# car.net
KiCad netlist of a schematic drawn in Altium Designer
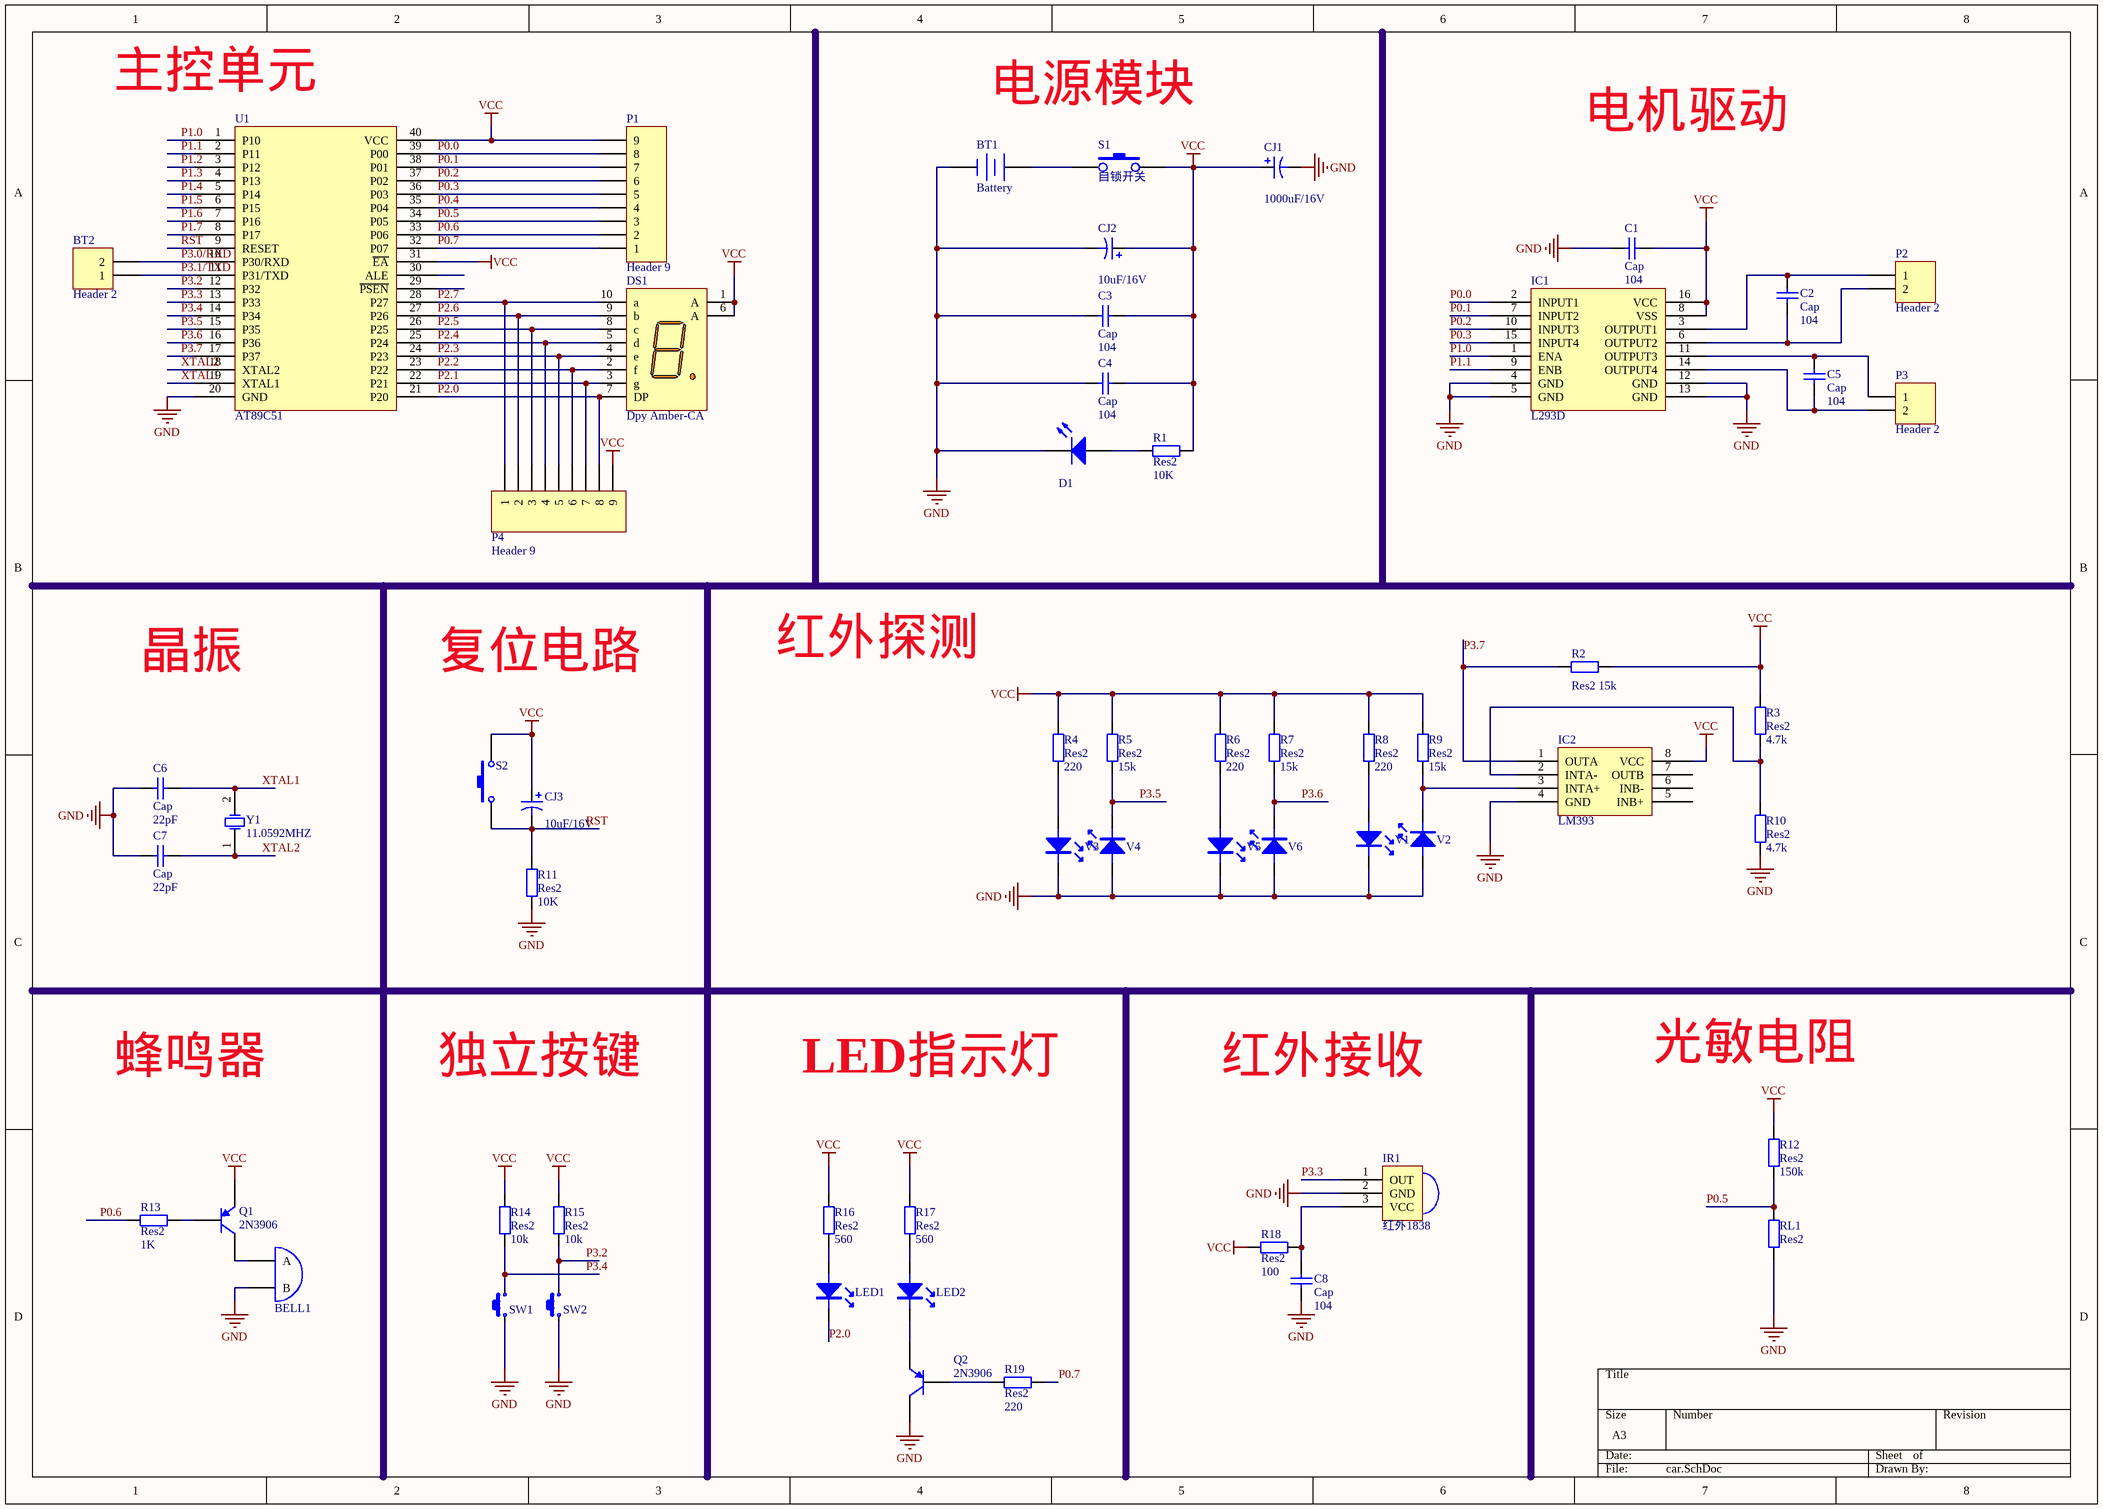
[diagram p0: car.SchDoc]

(export (version "E")
  (design (tool "Eeschema 10.0.6"))
  (components
    (comp (ref "BELL1") (value "BELL") (footprint "BELL") (libsource (lib "SQ-1") (part "BELL")))
    (comp (ref "BT1")
      (value "Battery")
      (footprint "BAT-2")
      (description "Multicell Battery")
      (fields (field (name "PUBLISHER") "Altium Limited"))
      (libsource (lib "Miscellaneous Devices") (part "Battery"))
    )
    (comp (ref "BT2")
      (value "Header 2")
      (footprint "HDR1X2")
      (description "Header, 2-Pin")
      (fields (field (name "PUBLISHER") "Altium Limited"))
      (libsource (lib "") (part "Header 2_1"))
    )
    (comp (ref "C1")
      (value "Cap")
      (footprint "0805C")
      (description "Capacitor")
      (fields (field (name "ALTIUM_VALUE") "104") (field (name "PUBLISHER") "Altium Limited"))
      (libsource (lib "Miscellaneous Devices") (part "Cap"))
    )
    (comp (ref "C2")
      (value "Cap")
      (footprint "0805C")
      (description "Capacitor")
      (fields (field (name "ALTIUM_VALUE") "104") (field (name "PUBLISHER") "Altium Limited"))
      (libsource (lib "Miscellaneous Devices") (part "Cap"))
    )
    (comp (ref "C3")
      (value "Cap")
      (footprint "0805C")
      (description "Capacitor")
      (fields (field (name "ALTIUM_VALUE") "104") (field (name "PUBLISHER") "Altium Limited"))
      (libsource (lib "Miscellaneous Devices") (part "Cap"))
    )
    (comp (ref "C4")
      (value "Cap")
      (footprint "0805C")
      (description "Capacitor")
      (fields (field (name "ALTIUM_VALUE") "104") (field (name "PUBLISHER") "Altium Limited"))
      (libsource (lib "Miscellaneous Devices") (part "Cap"))
    )
    (comp (ref "C5")
      (value "Cap")
      (footprint "0805C")
      (description "Capacitor")
      (fields (field (name "ALTIUM_VALUE") "104") (field (name "PUBLISHER") "Altium Limited"))
      (libsource (lib "Miscellaneous Devices") (part "Cap"))
    )
    (comp (ref "C6")
      (value "Cap")
      (footprint "0805C")
      (description "Capacitor")
      (fields (field (name "ALTIUM_VALUE") "22pF") (field (name "PUBLISHER") "Altium Limited"))
      (libsource (lib "Miscellaneous Devices") (part "Cap"))
    )
    (comp (ref "C7")
      (value "Cap")
      (footprint "0805C")
      (description "Capacitor")
      (fields (field (name "ALTIUM_VALUE") "22pF") (field (name "PUBLISHER") "Altium Limited"))
      (libsource (lib "Miscellaneous Devices") (part "Cap"))
    )
    (comp (ref "C8")
      (value "Cap")
      (footprint "0805C")
      (description "Capacitor")
      (fields (field (name "ALTIUM_VALUE") "104") (field (name "PUBLISHER") "Altium Limited"))
      (libsource (lib "Miscellaneous Devices") (part "Cap"))
    )
    (comp (ref "CJ1")
      (value "1000uF/16V")
      (footprint "RB10U")
      (description "Polarized Capacitor (Radial)")
      (fields (field (name "PUBLISHER") "Altium Limited"))
      (libsource (lib "Miscellaneous Devices") (part "Cap Pol1"))
    )
    (comp (ref "CJ2")
      (value "10uF/16V")
      (footprint "RB10U")
      (description "Polarized Capacitor (Radial)")
      (fields (field (name "PUBLISHER") "Altium Limited"))
      (libsource (lib "Miscellaneous Devices") (part "Cap Pol1"))
    )
    (comp (ref "CJ3")
      (value "10uF/16V")
      (footprint "RB10U")
      (description "Polarized Capacitor (Radial)")
      (fields (field (name "PUBLISHER") "Altium Limited"))
      (libsource (lib "Miscellaneous Devices") (part "Cap Pol1"))
    )
    (comp (ref "D1")
      (value "LED0")
      (footprint "0805-LED")
      (description "Typical INFRARED GaAs LED")
      (fields (field (name "PUBLISHER") "Altium Limited"))
      (libsource (lib "Miscellaneous Devices") (part "LED0"))
    )
    (comp (ref "DS1")
      (value "Dpy Amber-CA")
      (footprint "A")
      (description "7.62 mm Black Surface Orange 7-Segment Display: CA, RH DP")
      (fields (field (name "PUBLISHER") "Altium Limited"))
      (libsource (lib "Miscellaneous Devices") (part "Dpy Amber-CA"))
    )
    (comp (ref "IC1") (value "L293D") (footprint "L293D") (libsource (lib "SQ-1") (part "L293D")))
    (comp (ref "IC2") (value "LM393") (footprint "LM393") (libsource (lib "SQ-1") (part "LM393")))
    (comp (ref "IR1") (value "红外1838") (footprint "红外1838") (libsource (lib "SQ-1") (part "红外1838")))
    (comp (ref "LED1") (value "LED") (footprint "0805-LED") (libsource (lib "SQ-1") (part "LED")))
    (comp (ref "LED2") (value "LED") (footprint "0805-LED") (libsource (lib "SQ-1") (part "LED")))
    (comp (ref "P1")
      (value "Header 9")
      (footprint "HDR1X9")
      (description "Header, 9-Pin")
      (fields (field (name "PUBLISHER") "Altium Limited"))
      (libsource (lib "") (part "Header 9_1"))
    )
    (comp (ref "P2")
      (value "Header 2")
      (footprint "HDR1X2")
      (description "Header, 2-Pin")
      (fields (field (name "PUBLISHER") "Altium Limited"))
      (libsource (lib "Miscellaneous Connectors") (part "Header 2"))
    )
    (comp (ref "P3")
      (value "Header 2")
      (footprint "HDR1X2")
      (description "Header, 2-Pin")
      (fields (field (name "PUBLISHER") "Altium Limited"))
      (libsource (lib "Miscellaneous Connectors") (part "Header 2"))
    )
    (comp (ref "P4")
      (value "Header 9")
      (footprint "HDR1X9")
      (description "Header, 9-Pin")
      (fields (field (name "PUBLISHER") "Altium Limited"))
      (libsource (lib "Miscellaneous Connectors") (part "Header 9"))
    )
    (comp (ref "Q1")
      (value "2N3906")
      (footprint "TO-92A")
      (description "PNP General Purpose Amplifier")
      (fields (field (name "PUBLISHER") "Altium Limited"))
      (libsource (lib "Miscellaneous Devices") (part "2N3906"))
    )
    (comp (ref "Q2")
      (value "2N3906")
      (footprint "TO-92A")
      (description "PNP General Purpose Amplifier")
      (fields (field (name "PUBLISHER") "Altium Limited"))
      (libsource (lib "Miscellaneous Devices") (part "2N3906"))
    )
    (comp (ref "R1")
      (value "Res2")
      (footprint "0805")
      (description "Resistor")
      (fields (field (name "ALTIUM_VALUE") "10K") (field (name "PUBLISHER") "Altium Limited"))
      (libsource (lib "") (part "Res2_2"))
    )
    (comp (ref "R2")
      (value "Res2")
      (footprint "0805")
      (description "Resistor")
      (fields (field (name "ALTIUM_VALUE") "15k") (field (name "PUBLISHER") "Altium Limited"))
      (libsource (lib "") (part "Res2_3"))
    )
    (comp (ref "R3")
      (value "Res2")
      (footprint "0805")
      (description "Resistor")
      (fields (field (name "ALTIUM_VALUE") "4.7k") (field (name "PUBLISHER") "Altium Limited"))
      (libsource (lib "") (part "Res2_1"))
    )
    (comp (ref "R4")
      (value "Res2")
      (footprint "0805")
      (description "Resistor")
      (fields (field (name "ALTIUM_VALUE") "220") (field (name "PUBLISHER") "Altium Limited"))
      (libsource (lib "Miscellaneous Devices") (part "Res2"))
    )
    (comp (ref "R5")
      (value "Res2")
      (footprint "0805")
      (description "Resistor")
      (fields (field (name "ALTIUM_VALUE") "15k") (field (name "PUBLISHER") "Altium Limited"))
      (libsource (lib "Miscellaneous Devices") (part "Res2"))
    )
    (comp (ref "R6")
      (value "Res2")
      (footprint "0805")
      (description "Resistor")
      (fields (field (name "ALTIUM_VALUE") "220") (field (name "PUBLISHER") "Altium Limited"))
      (libsource (lib "Miscellaneous Devices") (part "Res2"))
    )
    (comp (ref "R7")
      (value "Res2")
      (footprint "0805")
      (description "Resistor")
      (fields (field (name "ALTIUM_VALUE") "15k") (field (name "PUBLISHER") "Altium Limited"))
      (libsource (lib "Miscellaneous Devices") (part "Res2"))
    )
    (comp (ref "R8")
      (value "Res2")
      (footprint "0805")
      (description "Resistor")
      (fields (field (name "ALTIUM_VALUE") "220") (field (name "PUBLISHER") "Altium Limited"))
      (libsource (lib "Miscellaneous Devices") (part "Res2"))
    )
    (comp (ref "R9")
      (value "Res2")
      (footprint "0805")
      (description "Resistor")
      (fields (field (name "ALTIUM_VALUE") "15k") (field (name "PUBLISHER") "Altium Limited"))
      (libsource (lib "Miscellaneous Devices") (part "Res2"))
    )
    (comp (ref "R10")
      (value "Res2")
      (footprint "0805")
      (description "Resistor")
      (fields (field (name "ALTIUM_VALUE") "4.7k") (field (name "PUBLISHER") "Altium Limited"))
      (libsource (lib "") (part "Res2_1"))
    )
    (comp (ref "R11")
      (value "Res2")
      (footprint "0805")
      (description "Resistor")
      (fields (field (name "ALTIUM_VALUE") "10K") (field (name "PUBLISHER") "Altium Limited"))
      (libsource (lib "") (part "Res2_1"))
    )
    (comp (ref "R12")
      (value "Res2")
      (footprint "0805")
      (description "Resistor")
      (fields (field (name "ALTIUM_VALUE") "150k") (field (name "PUBLISHER") "Altium Limited"))
      (libsource (lib "Miscellaneous Devices") (part "Res2"))
    )
    (comp (ref "R13")
      (value "Res2")
      (footprint "0805")
      (description "Resistor")
      (fields (field (name "ALTIUM_VALUE") "1K") (field (name "PUBLISHER") "Altium Limited"))
      (libsource (lib "") (part "Res2_2"))
    )
    (comp (ref "R14")
      (value "Res2")
      (footprint "0805")
      (description "Resistor")
      (fields (field (name "ALTIUM_VALUE") "10k") (field (name "PUBLISHER") "Altium Limited"))
      (libsource (lib "Miscellaneous Devices") (part "Res2"))
    )
    (comp (ref "R15")
      (value "Res2")
      (footprint "0805")
      (description "Resistor")
      (fields (field (name "ALTIUM_VALUE") "10k") (field (name "PUBLISHER") "Altium Limited"))
      (libsource (lib "Miscellaneous Devices") (part "Res2"))
    )
    (comp (ref "R16")
      (value "Res2")
      (footprint "0805")
      (description "Resistor")
      (fields (field (name "ALTIUM_VALUE") "560") (field (name "PUBLISHER") "Altium Limited"))
      (libsource (lib "Miscellaneous Devices") (part "Res2"))
    )
    (comp (ref "R17")
      (value "Res2")
      (footprint "0805")
      (description "Resistor")
      (fields (field (name "ALTIUM_VALUE") "560") (field (name "PUBLISHER") "Altium Limited"))
      (libsource (lib "Miscellaneous Devices") (part "Res2"))
    )
    (comp (ref "R18")
      (value "Res2")
      (footprint "0805")
      (description "Resistor")
      (fields (field (name "ALTIUM_VALUE") "100") (field (name "PUBLISHER") "Altium Limited"))
      (libsource (lib "") (part "Res2_2"))
    )
    (comp (ref "R19")
      (value "Res2")
      (footprint "0805")
      (description "Resistor")
      (fields (field (name "ALTIUM_VALUE") "220") (field (name "PUBLISHER") "Altium Limited"))
      (libsource (lib "") (part "Res2_3"))
    )
    (comp (ref "RL1")
      (value "Res2")
      (footprint "AXIAL-0.4")
      (description "Resistor")
      (fields (field (name "PUBLISHER") "Altium Limited"))
      (libsource (lib "") (part "Res2_1"))
    )
    (comp (ref "S1") (value "自锁开关") (footprint "自锁开关") (libsource (lib "SQ-1") (part "自锁开关")))
    (comp (ref "S2")
      (value "~")
      (footprint "SWD")
      (description "Switch")
      (fields (field (name "PUBLISHER") "Altium Limited"))
      (libsource (lib "Miscellaneous Devices") (part "SW-PB"))
    )
    (comp (ref "SW1") (value "SW") (footprint "SWD") (libsource (lib "SQ-1") (part "SW")))
    (comp (ref "SW2") (value "SW") (footprint "SWD") (libsource (lib "SQ-1") (part "SW")))
    (comp (ref "U1") (value "AT89C51") (footprint "89c52") (libsource (lib "SQ-1") (part "AT89C51")))
    (comp (ref "V1") (value "红外管") (footprint "红外管") (libsource (lib "SQ-1") (part "LED")))
    (comp (ref "V2") (value "红外管") (footprint "红外管") (libsource (lib "SQ-1") (part "LED")))
    (comp (ref "V3") (value "红外管") (footprint "红外管") (libsource (lib "SQ-1") (part "LED")))
    (comp (ref "V4") (value "红外管") (footprint "红外管") (libsource (lib "SQ-1") (part "LED")))
    (comp (ref "V5") (value "红外管") (footprint "红外管") (libsource (lib "SQ-1") (part "LED")))
    (comp (ref "V6") (value "红外管") (footprint "红外管") (libsource (lib "SQ-1") (part "LED")))
    (comp (ref "Y1")
      (value "11.0592MHZ")
      (footprint "XTAL")
      (description "Crystal Oscillator")
      (fields (field (name "PUBLISHER") "Altium Limited"))
      (libsource (lib "Miscellaneous Devices") (part "XTAL"))
    )
  )
  (nets
    (net (code "1") (name "/P0.0") (class "Default")
      (node (ref "IC1") (pin "2") (pinfunction "INPUT1_2") (pintype "passive"))
      (node (ref "P1") (pin "8") (pinfunction "8_8") (pintype "passive"))
      (node (ref "U1") (pin "39") (pinfunction "P00_39") (pintype "passive"))
    )
    (net (code "2") (name "/P0.1") (class "Default")
      (node (ref "IC1") (pin "7") (pinfunction "INPUT2_7") (pintype "passive"))
      (node (ref "P1") (pin "7") (pinfunction "7_7") (pintype "passive"))
      (node (ref "U1") (pin "38") (pinfunction "P01_38") (pintype "passive"))
    )
    (net (code "3") (name "/P0.2") (class "Default")
      (node (ref "IC1") (pin "10") (pinfunction "INPUT3_10") (pintype "passive"))
      (node (ref "P1") (pin "6") (pinfunction "6_6") (pintype "passive"))
      (node (ref "U1") (pin "37") (pinfunction "P02_37") (pintype "passive"))
    )
    (net (code "4") (name "/P0.3") (class "Default")
      (node (ref "IC1") (pin "15") (pinfunction "INPUT4_15") (pintype "passive"))
      (node (ref "P1") (pin "5") (pinfunction "5_5") (pintype "passive"))
      (node (ref "U1") (pin "36") (pinfunction "P03_36") (pintype "passive"))
    )
    (net (code "5") (name "/P0.4") (class "Default")
      (node (ref "P1") (pin "4") (pinfunction "4_4") (pintype "passive"))
      (node (ref "U1") (pin "35") (pinfunction "P04_35") (pintype "passive"))
    )
    (net (code "6") (name "/P0.5") (class "Default")
      (node (ref "P1") (pin "3") (pinfunction "3_3") (pintype "passive"))
      (node (ref "R12") (pin "2") (pinfunction "2_2") (pintype "passive"))
      (node (ref "RL1") (pin "2") (pinfunction "2_2") (pintype "passive"))
      (node (ref "U1") (pin "34") (pinfunction "P05_34") (pintype "passive"))
    )
    (net (code "7") (name "/P0.6") (class "Default")
      (node (ref "P1") (pin "2") (pinfunction "2_2") (pintype "passive"))
      (node (ref "R13") (pin "2") (pinfunction "2_2") (pintype "passive"))
      (node (ref "U1") (pin "33") (pinfunction "P06_33") (pintype "passive"))
    )
    (net (code "8") (name "/P0.7") (class "Default")
      (node (ref "P1") (pin "1") (pinfunction "1_1") (pintype "passive"))
      (node (ref "R19") (pin "2") (pinfunction "2_2") (pintype "passive"))
      (node (ref "U1") (pin "32") (pinfunction "P07_32") (pintype "passive"))
    )
    (net (code "9") (name "/P1.0") (class "Default")
      (node (ref "IC1") (pin "1") (pinfunction "ENA_1") (pintype "passive"))
      (node (ref "U1") (pin "1") (pinfunction "P10_1") (pintype "passive"))
    )
    (net (code "10") (name "/P1.1") (class "Default")
      (node (ref "IC1") (pin "9") (pinfunction "ENB_9") (pintype "passive"))
      (node (ref "U1") (pin "2") (pinfunction "P11_2") (pintype "passive"))
    )
    (net (code "11") (name "/P1.2") (class "Default")
      (node (ref "U1") (pin "3") (pinfunction "P12_3") (pintype "passive"))
    )
    (net (code "12") (name "/P1.3") (class "Default")
      (node (ref "U1") (pin "4") (pinfunction "P13_4") (pintype "passive"))
    )
    (net (code "13") (name "/P1.4") (class "Default")
      (node (ref "U1") (pin "5") (pinfunction "P14_5") (pintype "passive"))
    )
    (net (code "14") (name "/P1.5") (class "Default")
      (node (ref "U1") (pin "6") (pinfunction "P15_6") (pintype "passive"))
    )
    (net (code "15") (name "/P1.6") (class "Default")
      (node (ref "U1") (pin "7") (pinfunction "P16_7") (pintype "passive"))
    )
    (net (code "16") (name "/P1.7") (class "Default")
      (node (ref "U1") (pin "8") (pinfunction "P17_8") (pintype "passive"))
    )
    (net (code "17") (name "/P2.0") (class "Default")
      (node (ref "DS1") (pin "7") (pinfunction "DP_7") (pintype "passive"))
      (node (ref "LED1") (pin "2") (pinfunction "2_2") (pintype "passive"))
      (node (ref "P4") (pin "8") (pinfunction "8_8") (pintype "passive"))
      (node (ref "U1") (pin "21") (pinfunction "P20_21") (pintype "passive"))
    )
    (net (code "18") (name "/P2.1") (class "Default")
      (node (ref "DS1") (pin "3") (pinfunction "g_3") (pintype "passive"))
      (node (ref "P4") (pin "7") (pinfunction "7_7") (pintype "passive"))
      (node (ref "U1") (pin "22") (pinfunction "P21_22") (pintype "passive"))
    )
    (net (code "19") (name "/P2.2") (class "Default")
      (node (ref "DS1") (pin "2") (pinfunction "f_2") (pintype "passive"))
      (node (ref "P4") (pin "6") (pinfunction "6_6") (pintype "passive"))
      (node (ref "U1") (pin "23") (pinfunction "P22_23") (pintype "passive"))
    )
    (net (code "20") (name "/P2.3") (class "Default")
      (node (ref "DS1") (pin "4") (pinfunction "e_4") (pintype "passive"))
      (node (ref "P4") (pin "5") (pinfunction "5_5") (pintype "passive"))
      (node (ref "U1") (pin "24") (pinfunction "P23_24") (pintype "passive"))
    )
    (net (code "21") (name "/P2.4") (class "Default")
      (node (ref "DS1") (pin "5") (pinfunction "d_5") (pintype "passive"))
      (node (ref "P4") (pin "4") (pinfunction "4_4") (pintype "passive"))
      (node (ref "U1") (pin "25") (pinfunction "P24_25") (pintype "passive"))
    )
    (net (code "22") (name "/P2.5") (class "Default")
      (node (ref "DS1") (pin "8") (pinfunction "c_8") (pintype "passive"))
      (node (ref "P4") (pin "3") (pinfunction "3_3") (pintype "passive"))
      (node (ref "U1") (pin "26") (pinfunction "P25_26") (pintype "passive"))
    )
    (net (code "23") (name "/P2.6") (class "Default")
      (node (ref "DS1") (pin "9") (pinfunction "b_9") (pintype "passive"))
      (node (ref "P4") (pin "2") (pinfunction "2_2") (pintype "passive"))
      (node (ref "U1") (pin "27") (pinfunction "P26_27") (pintype "passive"))
    )
    (net (code "24") (name "/P2.7") (class "Default")
      (node (ref "DS1") (pin "10") (pinfunction "a_10") (pintype "passive"))
      (node (ref "P4") (pin "1") (pinfunction "1_1") (pintype "passive"))
      (node (ref "U1") (pin "28") (pinfunction "P27_28") (pintype "passive"))
    )
    (net (code "25") (name "/P3.0{slash}RXD") (class "Default")
      (node (ref "BT2") (pin "2") (pinfunction "2_2") (pintype "passive"))
      (node (ref "U1") (pin "10") (pinfunction "P30/RXD_10") (pintype "passive"))
    )
    (net (code "26") (name "/P3.1{slash}TXD") (class "Default")
      (node (ref "BT2") (pin "1") (pinfunction "1_1") (pintype "passive"))
      (node (ref "U1") (pin "11") (pinfunction "P31/TXD_11") (pintype "passive"))
    )
    (net (code "27") (name "/P3.2") (class "Default")
      (node (ref "R15") (pin "2") (pinfunction "2_2") (pintype "passive"))
      (node (ref "SW2") (pin "2") (pinfunction "2_2") (pintype "passive"))
      (node (ref "U1") (pin "12") (pinfunction "P32_12") (pintype "passive"))
    )
    (net (code "28") (name "/P3.3") (class "Default")
      (node (ref "IR1") (pin "1") (pinfunction "OUT_1") (pintype "passive"))
      (node (ref "U1") (pin "13") (pinfunction "P33_13") (pintype "passive"))
    )
    (net (code "29") (name "/P3.4") (class "Default")
      (node (ref "R14") (pin "2") (pinfunction "2_2") (pintype "passive"))
      (node (ref "SW1") (pin "2") (pinfunction "2_2") (pintype "passive"))
      (node (ref "U1") (pin "14") (pinfunction "P34_14") (pintype "passive"))
    )
    (net (code "30") (name "/P3.5") (class "Default")
      (node (ref "R5") (pin "2") (pinfunction "2_2") (pintype "passive"))
      (node (ref "U1") (pin "15") (pinfunction "P35_15") (pintype "passive"))
      (node (ref "V4") (pin "2") (pinfunction "2_2") (pintype "passive"))
    )
    (net (code "31") (name "/P3.6") (class "Default")
      (node (ref "R7") (pin "2") (pinfunction "2_2") (pintype "passive"))
      (node (ref "U1") (pin "16") (pinfunction "P36_16") (pintype "passive"))
      (node (ref "V6") (pin "2") (pinfunction "2_2") (pintype "passive"))
    )
    (net (code "32") (name "/P3.7") (class "Default")
      (node (ref "IC2") (pin "1") (pinfunction "OUTA_1") (pintype "passive"))
      (node (ref "R2") (pin "1") (pinfunction "1_1") (pintype "passive"))
      (node (ref "U1") (pin "17") (pinfunction "P37_17") (pintype "passive"))
    )
    (net (code "33") (name "/RST") (class "Default")
      (node (ref "CJ3") (pin "2") (pinfunction "2_2") (pintype "passive"))
      (node (ref "R11") (pin "2") (pinfunction "2_2") (pintype "passive"))
      (node (ref "S2") (pin "1") (pinfunction "1_1") (pintype "passive"))
      (node (ref "U1") (pin "9") (pinfunction "RESET_9") (pintype "passive"))
    )
    (net (code "34") (name "/XTAL1") (class "Default")
      (node (ref "C6") (pin "2") (pinfunction "2_2") (pintype "passive"))
      (node (ref "U1") (pin "19") (pinfunction "XTAL1_19") (pintype "passive"))
      (node (ref "Y1") (pin "2") (pinfunction "OSC2_2") (pintype "passive"))
    )
    (net (code "35") (name "/XTAL2") (class "Default")
      (node (ref "C7") (pin "2") (pinfunction "2_2") (pintype "passive"))
      (node (ref "U1") (pin "18") (pinfunction "XTAL2_18") (pintype "passive"))
      (node (ref "Y1") (pin "1") (pinfunction "OSC1_1") (pintype "passive"))
    )
    (net (code "36") (name "GND") (class "Default")
      (node (ref "BELL1") (pin "2") (pinfunction "B_2") (pintype "passive"))
      (node (ref "BT1") (pin "2") (pinfunction "-_2") (pintype "passive"))
      (node (ref "C1") (pin "1") (pinfunction "1_1") (pintype "passive"))
      (node (ref "C3") (pin "1") (pinfunction "1_1") (pintype "passive"))
      (node (ref "C4") (pin "1") (pinfunction "1_1") (pintype "passive"))
      (node (ref "C6") (pin "1") (pinfunction "1_1") (pintype "passive"))
      (node (ref "C7") (pin "1") (pinfunction "1_1") (pintype "passive"))
      (node (ref "C8") (pin "1") (pinfunction "1_1") (pintype "passive"))
      (node (ref "CJ1") (pin "2") (pinfunction "2_2") (pintype "passive"))
      (node (ref "CJ2") (pin "2") (pinfunction "2_2") (pintype "passive"))
      (node (ref "D1") (pin "2") (pinfunction "K_2") (pintype "passive"))
      (node (ref "IC1") (pin "12") (pinfunction "GND_12") (pintype "passive"))
      (node (ref "IC1") (pin "13") (pinfunction "GND_13") (pintype "passive"))
      (node (ref "IC1") (pin "4") (pinfunction "GND_4") (pintype "passive"))
      (node (ref "IC1") (pin "5") (pinfunction "GND_5") (pintype "passive"))
      (node (ref "IC2") (pin "4") (pinfunction "GND_4") (pintype "passive"))
      (node (ref "IR1") (pin "2") (pinfunction "GND_2") (pintype "passive"))
      (node (ref "Q2") (pin "3") (pinfunction "C_3") (pintype "passive"))
      (node (ref "R10") (pin "1") (pinfunction "1_1") (pintype "passive"))
      (node (ref "R11") (pin "1") (pinfunction "1_1") (pintype "passive"))
      (node (ref "RL1") (pin "1") (pinfunction "1_1") (pintype "passive"))
      (node (ref "SW1") (pin "1") (pinfunction "1_1") (pintype "passive"))
      (node (ref "SW2") (pin "1") (pinfunction "1_1") (pintype "passive"))
      (node (ref "U1") (pin "20") (pinfunction "GND_20") (pintype "passive"))
      (node (ref "V1") (pin "2") (pinfunction "2_2") (pintype "passive"))
      (node (ref "V2") (pin "1") (pinfunction "1_1") (pintype "passive"))
      (node (ref "V3") (pin "2") (pinfunction "2_2") (pintype "passive"))
      (node (ref "V4") (pin "1") (pinfunction "1_1") (pintype "passive"))
      (node (ref "V5") (pin "2") (pinfunction "2_2") (pintype "passive"))
      (node (ref "V6") (pin "1") (pinfunction "1_1") (pintype "passive"))
    )
    (net (code "37") (name "Net-(BELL1-A)") (class "Default")
      (node (ref "BELL1") (pin "1") (pinfunction "A_1") (pintype "passive"))
      (node (ref "Q1") (pin "3") (pinfunction "C_3") (pintype "passive"))
    )
    (net (code "38") (name "Net-(BT1-+)") (class "Default")
      (node (ref "BT1") (pin "1") (pinfunction "+_1") (pintype "passive"))
      (node (ref "S1") (pin "3") (pinfunction "3_3") (pintype "passive"))
    )
    (net (code "39") (name "Net-(D1-A)") (class "Default")
      (node (ref "D1") (pin "1") (pinfunction "A_1") (pintype "passive"))
      (node (ref "R1") (pin "2") (pinfunction "2_2") (pintype "passive"))
    )
    (net (code "40") (name "Net-(IC1-OUTPUT1)") (class "Default")
      (node (ref "C2") (pin "2") (pinfunction "2_2") (pintype "passive"))
      (node (ref "IC1") (pin "3") (pinfunction "OUTPUT1_3") (pintype "passive"))
      (node (ref "P2") (pin "1") (pinfunction "1_1") (pintype "passive"))
    )
    (net (code "41") (name "Net-(IC1-OUTPUT2)") (class "Default")
      (node (ref "C2") (pin "1") (pinfunction "1_1") (pintype "passive"))
      (node (ref "IC1") (pin "6") (pinfunction "OUTPUT2_6") (pintype "passive"))
      (node (ref "P2") (pin "2") (pinfunction "2_2") (pintype "passive"))
    )
    (net (code "42") (name "Net-(IC1-OUTPUT3)") (class "Default")
      (node (ref "C5") (pin "2") (pinfunction "2_2") (pintype "passive"))
      (node (ref "IC1") (pin "11") (pinfunction "OUTPUT3_11") (pintype "passive"))
      (node (ref "P3") (pin "1") (pinfunction "1_1") (pintype "passive"))
    )
    (net (code "43") (name "Net-(IC1-OUTPUT4)") (class "Default")
      (node (ref "C5") (pin "1") (pinfunction "1_1") (pintype "passive"))
      (node (ref "IC1") (pin "14") (pinfunction "OUTPUT4_14") (pintype "passive"))
      (node (ref "P3") (pin "2") (pinfunction "2_2") (pintype "passive"))
    )
    (net (code "44") (name "Net-(IC2-INTA+)") (class "Default")
      (node (ref "IC2") (pin "3") (pinfunction "INTA+_3") (pintype "passive"))
      (node (ref "R9") (pin "2") (pinfunction "2_2") (pintype "passive"))
      (node (ref "V2") (pin "2") (pinfunction "2_2") (pintype "passive"))
    )
    (net (code "45") (name "Net-(IC2-INTA-)") (class "Default")
      (node (ref "IC2") (pin "2") (pinfunction "INTA-_2") (pintype "passive"))
      (node (ref "R10") (pin "2") (pinfunction "2_2") (pintype "passive"))
      (node (ref "R3") (pin "1") (pinfunction "1_1") (pintype "passive"))
    )
    (net (code "46") (name "Net-(IR1-VCC)") (class "Default")
      (node (ref "C8") (pin "2") (pinfunction "2_2") (pintype "passive"))
      (node (ref "IR1") (pin "3") (pinfunction "VCC_3") (pintype "passive"))
      (node (ref "R18") (pin "1") (pinfunction "1_1") (pintype "passive"))
    )
    (net (code "47") (name "Net-(LED1-Pad1)") (class "Default")
      (node (ref "LED1") (pin "1") (pinfunction "1_1") (pintype "passive"))
      (node (ref "R16") (pin "2") (pinfunction "2_2") (pintype "passive"))
    )
    (net (code "48") (name "Net-(LED2-Pad1)") (class "Default")
      (node (ref "LED2") (pin "1") (pinfunction "1_1") (pintype "passive"))
      (node (ref "R17") (pin "2") (pinfunction "2_2") (pintype "passive"))
    )
    (net (code "49") (name "Net-(Q1-B)") (class "Default")
      (node (ref "Q1") (pin "2") (pinfunction "B_2") (pintype "passive"))
      (node (ref "R13") (pin "1") (pinfunction "1_1") (pintype "passive"))
    )
    (net (code "50") (name "Net-(Q2-B)") (class "Default")
      (node (ref "Q2") (pin "2") (pinfunction "B_2") (pintype "passive"))
      (node (ref "R19") (pin "1") (pinfunction "1_1") (pintype "passive"))
    )
    (net (code "51") (name "Net-(Q2-E)") (class "Default")
      (node (ref "LED2") (pin "2") (pinfunction "2_2") (pintype "passive"))
      (node (ref "Q2") (pin "1") (pinfunction "E_1") (pintype "passive"))
    )
    (net (code "52") (name "Net-(R4-Pad2)") (class "Default")
      (node (ref "R4") (pin "2") (pinfunction "2_2") (pintype "passive"))
      (node (ref "V3") (pin "1") (pinfunction "1_1") (pintype "passive"))
    )
    (net (code "53") (name "Net-(R6-Pad2)") (class "Default")
      (node (ref "R6") (pin "2") (pinfunction "2_2") (pintype "passive"))
      (node (ref "V5") (pin "1") (pinfunction "1_1") (pintype "passive"))
    )
    (net (code "54") (name "Net-(R8-Pad2)") (class "Default")
      (node (ref "R8") (pin "2") (pinfunction "2_2") (pintype "passive"))
      (node (ref "V1") (pin "1") (pinfunction "1_1") (pintype "passive"))
    )
    (net (code "55") (name "VCC") (class "Default")
      (node (ref "C1") (pin "2") (pinfunction "2_2") (pintype "passive"))
      (node (ref "C3") (pin "2") (pinfunction "2_2") (pintype "passive"))
      (node (ref "C4") (pin "2") (pinfunction "2_2") (pintype "passive"))
      (node (ref "CJ1") (pin "1") (pinfunction "1_1") (pintype "passive"))
      (node (ref "CJ2") (pin "1") (pinfunction "1_1") (pintype "passive"))
      (node (ref "CJ3") (pin "1") (pinfunction "1_1") (pintype "passive"))
      (node (ref "DS1") (pin "1") (pinfunction "A_1") (pintype "passive"))
      (node (ref "DS1") (pin "6") (pinfunction "A_6") (pintype "passive"))
      (node (ref "IC1") (pin "16") (pinfunction "VCC_16") (pintype "passive"))
      (node (ref "IC1") (pin "8") (pinfunction "VSS_8") (pintype "passive"))
      (node (ref "IC2") (pin "8") (pinfunction "VCC_8") (pintype "passive"))
      (node (ref "P1") (pin "9") (pinfunction "9_9") (pintype "passive"))
      (node (ref "P4") (pin "9") (pinfunction "9_9") (pintype "passive"))
      (node (ref "Q1") (pin "1") (pinfunction "E_1") (pintype "passive"))
      (node (ref "R1") (pin "1") (pinfunction "1_1") (pintype "passive"))
      (node (ref "R12") (pin "1") (pinfunction "1_1") (pintype "passive"))
      (node (ref "R14") (pin "1") (pinfunction "1_1") (pintype "passive"))
      (node (ref "R15") (pin "1") (pinfunction "1_1") (pintype "passive"))
      (node (ref "R16") (pin "1") (pinfunction "1_1") (pintype "passive"))
      (node (ref "R17") (pin "1") (pinfunction "1_1") (pintype "passive"))
      (node (ref "R18") (pin "2") (pinfunction "2_2") (pintype "passive"))
      (node (ref "R2") (pin "2") (pinfunction "2_2") (pintype "passive"))
      (node (ref "R3") (pin "2") (pinfunction "2_2") (pintype "passive"))
      (node (ref "R4") (pin "1") (pinfunction "1_1") (pintype "passive"))
      (node (ref "R5") (pin "1") (pinfunction "1_1") (pintype "passive"))
      (node (ref "R6") (pin "1") (pinfunction "1_1") (pintype "passive"))
      (node (ref "R7") (pin "1") (pinfunction "1_1") (pintype "passive"))
      (node (ref "R8") (pin "1") (pinfunction "1_1") (pintype "passive"))
      (node (ref "R9") (pin "1") (pinfunction "1_1") (pintype "passive"))
      (node (ref "S1") (pin "5") (pinfunction "5_5") (pintype "passive"))
      (node (ref "S2") (pin "2") (pinfunction "2_2") (pintype "passive"))
      (node (ref "U1") (pin "31") (pinfunction "~{EA}_31") (pintype "passive"))
      (node (ref "U1") (pin "40") (pinfunction "VCC_40") (pintype "passive"))
    )
    (net (code "56") (name "unconnected-(IC2-INB+-Pad5)") (class "Default")
      (node (ref "IC2") (pin "5") (pinfunction "INB+_5") (pintype "passive"))
    )
    (net (code "57") (name "unconnected-(IC2-INB--Pad6)") (class "Default")
      (node (ref "IC2") (pin "6") (pinfunction "INB-_6") (pintype "passive"))
    )
    (net (code "58") (name "unconnected-(IC2-OUTB-Pad7)") (class "Default")
      (node (ref "IC2") (pin "7") (pinfunction "OUTB_7") (pintype "passive"))
    )
    (net (code "59") (name "unconnected-(U1-ALE-Pad30)") (class "Default")
      (node (ref "U1") (pin "30") (pinfunction "ALE_30") (pintype "passive"))
    )
    (net (code "60") (name "unconnected-(U1-~{PSEN}-Pad29)") (class "Default")
      (node (ref "U1") (pin "29") (pinfunction "~{PSEN}_29") (pintype "passive"))
    )
  )
)
